# WallLightRemote_V1_0_HMI.net
KiCad netlist of a schematic drawn in Altium Designer
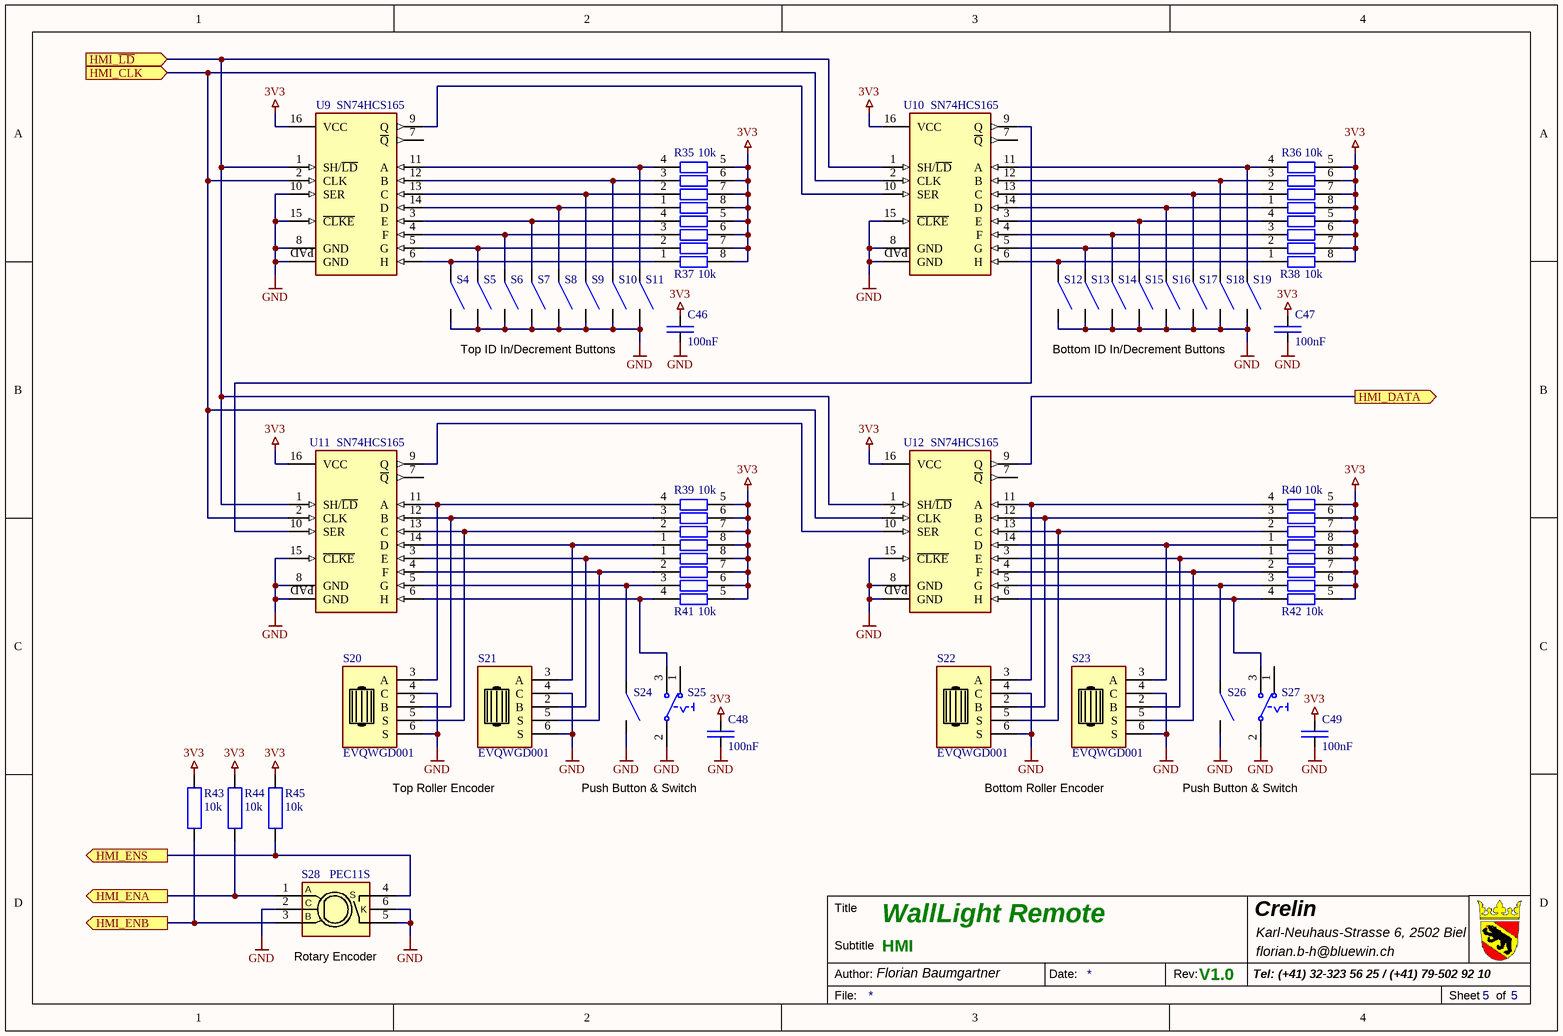
[diagram p0: WallLightRemote_V1.0_HMI.SchDoc]

(export (version "E")
  (design (tool "Eeschema 10.0.6"))
  (components
    (comp (ref "C46")
      (value "100nF")
      (footprint "SMD Keramikkondensator 0603")
      (description "SMD Ceramic Capacitor E6")
      (libsource (lib "Ceramic Capacitors-E6") (part "E6 - 100nF"))
    )
    (comp (ref "C47")
      (value "100nF")
      (footprint "SMD Keramikkondensator 0603")
      (description "SMD Ceramic Capacitor E6")
      (libsource (lib "Ceramic Capacitors-E6") (part "E6 - 100nF"))
    )
    (comp (ref "C48")
      (value "100nF")
      (footprint "SMD Keramikkondensator 0603")
      (description "SMD Ceramic Capacitor E6")
      (libsource (lib "Ceramic Capacitors-E6") (part "E6 - 100nF"))
    )
    (comp (ref "C49")
      (value "100nF")
      (footprint "SMD Keramikkondensator 0603")
      (description "SMD Ceramic Capacitor E6")
      (libsource (lib "Ceramic Capacitors-E6") (part "E6 - 100nF"))
    )
    (comp (ref "R35")
      (value "10k")
      (footprint "SMD Widerstand Array 4-Fach 0603")
      (description "Isolated Resistor Array")
      (libsource (lib "Fleet-Monitor") (part "R-Array Single Quad E24 - 10k"))
    )
    (comp (ref "R36")
      (value "10k")
      (footprint "SMD Widerstand Array 4-Fach 0603")
      (description "Isolated Resistor Array")
      (libsource (lib "Fleet-Monitor") (part "R-Array Single Quad E24 - 10k"))
    )
    (comp (ref "R37")
      (value "10k")
      (footprint "SMD Widerstand Array 4-Fach 0603")
      (description "Isolated Resistor Array")
      (libsource (lib "Fleet-Monitor") (part "R-Array Single Quad E24 - 10k"))
    )
    (comp (ref "R38")
      (value "10k")
      (footprint "SMD Widerstand Array 4-Fach 0603")
      (description "Isolated Resistor Array")
      (libsource (lib "Fleet-Monitor") (part "R-Array Single Quad E24 - 10k"))
    )
    (comp (ref "R39")
      (value "10k")
      (footprint "SMD Widerstand Array 4-Fach 0603")
      (description "Isolated Resistor Array")
      (libsource (lib "Fleet-Monitor") (part "R-Array Single Quad E24 - 10k"))
    )
    (comp (ref "R40")
      (value "10k")
      (footprint "SMD Widerstand Array 4-Fach 0603")
      (description "Isolated Resistor Array")
      (libsource (lib "Fleet-Monitor") (part "R-Array Single Quad E24 - 10k"))
    )
    (comp (ref "R41")
      (value "10k")
      (footprint "SMD Widerstand Array 4-Fach 0603")
      (description "Isolated Resistor Array")
      (libsource (lib "") (part "R-Array Single Quad E24 - 10k_1"))
    )
    (comp (ref "R42")
      (value "10k")
      (footprint "SMD Widerstand Array 4-Fach 0603")
      (description "Isolated Resistor Array")
      (libsource (lib "") (part "R-Array Single Quad E24 - 10k_1"))
    )
    (comp (ref "R43")
      (value "10k")
      (footprint "SMD Widerstand 0603")
      (description "RES (E=Heizwiderstand B=Messwandler)")
      (libsource (lib "TFS Integrated Library") (part "R-RESISTOR"))
    )
    (comp (ref "R44")
      (value "10k")
      (footprint "SMD Widerstand 0603")
      (description "RES (E=Heizwiderstand B=Messwandler)")
      (libsource (lib "TFS Integrated Library") (part "R-RESISTOR"))
    )
    (comp (ref "R45")
      (value "10k")
      (footprint "SMD Widerstand 0603")
      (description "RES (E=Heizwiderstand B=Messwandler)")
      (libsource (lib "TFS Integrated Library") (part "R-RESISTOR"))
    )
    (comp (ref "S4")
      (value "SMD-Button")
      (footprint "SMD Button 6.5x6.0x2.5")
      (description "Button SPST")
      (libsource (lib "Switches") (part "Button 3mmx2.5mm"))
    )
    (comp (ref "S5")
      (value "SMD-Button")
      (footprint "SMD Button 6.5x6.0x2.5")
      (description "Button SPST")
      (libsource (lib "Switches") (part "Button 3mmx2.5mm"))
    )
    (comp (ref "S6")
      (value "SMD-Button")
      (footprint "SMD Button 6.5x6.0x2.5")
      (description "Button SPST")
      (libsource (lib "Switches") (part "Button 3mmx2.5mm"))
    )
    (comp (ref "S7")
      (value "SMD-Button")
      (footprint "SMD Button 6.5x6.0x2.5")
      (description "Button SPST")
      (libsource (lib "Switches") (part "Button 3mmx2.5mm"))
    )
    (comp (ref "S8")
      (value "SMD-Button")
      (footprint "SMD Button 6.5x6.0x2.5")
      (description "Button SPST")
      (libsource (lib "Switches") (part "Button 3mmx2.5mm"))
    )
    (comp (ref "S9")
      (value "SMD-Button")
      (footprint "SMD Button 6.5x6.0x2.5")
      (description "Button SPST")
      (libsource (lib "Switches") (part "Button 3mmx2.5mm"))
    )
    (comp (ref "S10")
      (value "SMD-Button")
      (footprint "SMD Button 6.5x6.0x2.5")
      (description "Button SPST")
      (libsource (lib "Switches") (part "Button 3mmx2.5mm"))
    )
    (comp (ref "S11")
      (value "SMD-Button")
      (footprint "SMD Button 6.5x6.0x2.5")
      (description "Button SPST")
      (libsource (lib "Switches") (part "Button 3mmx2.5mm"))
    )
    (comp (ref "S12")
      (value "SMD-Button")
      (footprint "SMD Button 6.5x6.0x2.5")
      (description "Button SPST")
      (libsource (lib "Switches") (part "Button 3mmx2.5mm"))
    )
    (comp (ref "S13")
      (value "SMD-Button")
      (footprint "SMD Button 6.5x6.0x2.5")
      (description "Button SPST")
      (libsource (lib "Switches") (part "Button 3mmx2.5mm"))
    )
    (comp (ref "S14")
      (value "SMD-Button")
      (footprint "SMD Button 6.5x6.0x2.5")
      (description "Button SPST")
      (libsource (lib "Switches") (part "Button 3mmx2.5mm"))
    )
    (comp (ref "S15")
      (value "SMD-Button")
      (footprint "SMD Button 6.5x6.0x2.5")
      (description "Button SPST")
      (libsource (lib "Switches") (part "Button 3mmx2.5mm"))
    )
    (comp (ref "S16")
      (value "SMD-Button")
      (footprint "SMD Button 6.5x6.0x2.5")
      (description "Button SPST")
      (libsource (lib "Switches") (part "Button 3mmx2.5mm"))
    )
    (comp (ref "S17")
      (value "SMD-Button")
      (footprint "SMD Button 6.5x6.0x2.5")
      (description "Button SPST")
      (libsource (lib "Switches") (part "Button 3mmx2.5mm"))
    )
    (comp (ref "S18")
      (value "SMD-Button")
      (footprint "SMD Button 6.5x6.0x2.5")
      (description "Button SPST")
      (libsource (lib "Switches") (part "Button 3mmx2.5mm"))
    )
    (comp (ref "S19")
      (value "SMD-Button")
      (footprint "SMD Button 6.5x6.0x2.5")
      (description "Button SPST")
      (libsource (lib "Switches") (part "Button 3mmx2.5mm"))
    )
    (comp (ref "S20")
      (value "EVQWGD001")
      (footprint "THT Roller Encoder (EVQWGD001)")
      (description "Axial Roller Encoder")
      (libsource (lib "WallLightRemote") (part "S-EVQWGD001"))
    )
    (comp (ref "S21")
      (value "EVQWGD001")
      (footprint "THT Roller Encoder (EVQWGD001)")
      (description "Axial Roller Encoder")
      (libsource (lib "WallLightRemote") (part "S-EVQWGD001"))
    )
    (comp (ref "S22")
      (value "EVQWGD001")
      (footprint "THT Roller Encoder (EVQWGD001)")
      (description "Axial Roller Encoder")
      (libsource (lib "WallLightRemote") (part "S-EVQWGD001"))
    )
    (comp (ref "S23")
      (value "EVQWGD001")
      (footprint "THT Roller Encoder (EVQWGD001)")
      (description "Axial Roller Encoder")
      (libsource (lib "WallLightRemote") (part "S-EVQWGD001"))
    )
    (comp (ref "S24")
      (value "SMD-Button")
      (footprint "SMD Button 12.0x12.0x7.5")
      (description "Button SPST")
      (libsource (lib "Switches") (part "Button 3mmx2.5mm"))
    )
    (comp (ref "S25")
      (value "SS-12M11G5")
      (footprint "THT Slide Switch (MS12ANG03)")
      (description "Vertical Slide Switch SPDT")
      (libsource (lib "Custom ST-Link") (part "S-PCM12SMTR"))
    )
    (comp (ref "S26")
      (value "SMD-Button")
      (footprint "SMD Button 12.0x12.0x7.5")
      (description "Button SPST")
      (libsource (lib "Switches") (part "Button 3mmx2.5mm"))
    )
    (comp (ref "S27")
      (value "SS-12M11G5")
      (footprint "THT Slide Switch (MS12ANG03)")
      (description "Vertical Slide Switch SPDT")
      (libsource (lib "Custom ST-Link") (part "S-PCM12SMTR"))
    )
    (comp (ref "S28")
      (value "PEC11S")
      (footprint "SMD Rotary Encoder with Switch")
      (description "Rotary Encoder")
      (libsource (lib "WallLightRemote") (part "S-Rotary Encoder"))
    )
    (comp (ref "U9")
      (value "SN74HCS165")
      (footprint "SMD IC WQFN-16 (3.5x2.5)")
      (description "8-Bit Paralell-In Shift Register (Schmitt Trigger)")
      (libsource (lib "WallLightRemote") (part "U-SN74HCS165"))
    )
    (comp (ref "U10")
      (value "SN74HCS165")
      (footprint "SMD IC WQFN-16 (3.5x2.5)")
      (description "8-Bit Paralell-In Shift Register (Schmitt Trigger)")
      (libsource (lib "WallLightRemote") (part "U-SN74HCS165"))
    )
    (comp (ref "U11")
      (value "SN74HCS165")
      (footprint "SMD IC WQFN-16 (3.5x2.5)")
      (description "8-Bit Paralell-In Shift Register (Schmitt Trigger)")
      (libsource (lib "WallLightRemote") (part "U-SN74HCS165"))
    )
    (comp (ref "U12")
      (value "SN74HCS165")
      (footprint "SMD IC WQFN-16 (3.5x2.5)")
      (description "8-Bit Paralell-In Shift Register (Schmitt Trigger)")
      (libsource (lib "WallLightRemote") (part "U-SN74HCS165"))
    )
  )
  (nets
    (net (code "1") (name "/HMI_CLK") (class "Default")
      (node (ref "U10") (pin "2") (pinfunction "CLK_2") (pintype "input"))
      (node (ref "U11") (pin "2") (pinfunction "CLK_2") (pintype "input"))
      (node (ref "U12") (pin "2") (pinfunction "CLK_2") (pintype "input"))
      (node (ref "U9") (pin "2") (pinfunction "CLK_2") (pintype "input"))
    )
    (net (code "2") (name "/HMI_DATA") (class "Default")
      (node (ref "U12") (pin "9") (pinfunction "Q_9") (pintype "output"))
    )
    (net (code "3") (name "/HMI_ENA") (class "Default")
      (node (ref "R44") (pin "1") (pinfunction "1_1") (pintype "passive"))
      (node (ref "S28") (pin "1") (pinfunction "A_1") (pintype "passive"))
    )
    (net (code "4") (name "/HMI_ENB") (class "Default")
      (node (ref "R43") (pin "1") (pinfunction "1_1") (pintype "passive"))
      (node (ref "S28") (pin "3") (pinfunction "B_3") (pintype "passive"))
    )
    (net (code "5") (name "/HMI_ENS") (class "Default")
      (node (ref "R45") (pin "1") (pinfunction "1_1") (pintype "passive"))
      (node (ref "S28") (pin "4") (pinfunction "S_4") (pintype "passive"))
    )
    (net (code "6") (name "/HMI_~{LD}") (class "Default")
      (node (ref "U10") (pin "1") (pinfunction "SH/~{LD}_1") (pintype "input"))
      (node (ref "U11") (pin "1") (pinfunction "SH/~{LD}_1") (pintype "input"))
      (node (ref "U12") (pin "1") (pinfunction "SH/~{LD}_1") (pintype "input"))
      (node (ref "U9") (pin "1") (pinfunction "SH/~{LD}_1") (pintype "input"))
    )
    (net (code "7") (name "3V3") (class "Default")
      (node (ref "C46") (pin "2") (pinfunction "2_2") (pintype "passive"))
      (node (ref "C47") (pin "2") (pinfunction "2_2") (pintype "passive"))
      (node (ref "C48") (pin "2") (pinfunction "2_2") (pintype "passive"))
      (node (ref "C49") (pin "2") (pinfunction "2_2") (pintype "passive"))
      (node (ref "R35") (pin "5") (pinfunction "5_5") (pintype "passive"))
      (node (ref "R35") (pin "6") (pinfunction "6_6") (pintype "passive"))
      (node (ref "R35") (pin "7") (pinfunction "7_7") (pintype "passive"))
      (node (ref "R35") (pin "8") (pinfunction "8_8") (pintype "passive"))
      (node (ref "R36") (pin "5") (pinfunction "5_5") (pintype "passive"))
      (node (ref "R36") (pin "6") (pinfunction "6_6") (pintype "passive"))
      (node (ref "R36") (pin "7") (pinfunction "7_7") (pintype "passive"))
      (node (ref "R36") (pin "8") (pinfunction "8_8") (pintype "passive"))
      (node (ref "R37") (pin "5") (pinfunction "5_5") (pintype "passive"))
      (node (ref "R37") (pin "6") (pinfunction "6_6") (pintype "passive"))
      (node (ref "R37") (pin "7") (pinfunction "7_7") (pintype "passive"))
      (node (ref "R37") (pin "8") (pinfunction "8_8") (pintype "passive"))
      (node (ref "R38") (pin "5") (pinfunction "5_5") (pintype "passive"))
      (node (ref "R38") (pin "6") (pinfunction "6_6") (pintype "passive"))
      (node (ref "R38") (pin "7") (pinfunction "7_7") (pintype "passive"))
      (node (ref "R38") (pin "8") (pinfunction "8_8") (pintype "passive"))
      (node (ref "R39") (pin "5") (pinfunction "5_5") (pintype "passive"))
      (node (ref "R39") (pin "6") (pinfunction "6_6") (pintype "passive"))
      (node (ref "R39") (pin "7") (pinfunction "7_7") (pintype "passive"))
      (node (ref "R39") (pin "8") (pinfunction "8_8") (pintype "passive"))
      (node (ref "R40") (pin "5") (pinfunction "5_5") (pintype "passive"))
      (node (ref "R40") (pin "6") (pinfunction "6_6") (pintype "passive"))
      (node (ref "R40") (pin "7") (pinfunction "7_7") (pintype "passive"))
      (node (ref "R40") (pin "8") (pinfunction "8_8") (pintype "passive"))
      (node (ref "R41") (pin "5") (pinfunction "5_5") (pintype "passive"))
      (node (ref "R41") (pin "6") (pinfunction "6_6") (pintype "passive"))
      (node (ref "R41") (pin "7") (pinfunction "7_7") (pintype "passive"))
      (node (ref "R41") (pin "8") (pinfunction "8_8") (pintype "passive"))
      (node (ref "R42") (pin "5") (pinfunction "5_5") (pintype "passive"))
      (node (ref "R42") (pin "6") (pinfunction "6_6") (pintype "passive"))
      (node (ref "R42") (pin "7") (pinfunction "7_7") (pintype "passive"))
      (node (ref "R42") (pin "8") (pinfunction "8_8") (pintype "passive"))
      (node (ref "R43") (pin "2") (pinfunction "2_2") (pintype "passive"))
      (node (ref "R44") (pin "2") (pinfunction "2_2") (pintype "passive"))
      (node (ref "R45") (pin "2") (pinfunction "2_2") (pintype "passive"))
      (node (ref "U10") (pin "16") (pinfunction "VCC_16") (pintype "power_in"))
      (node (ref "U11") (pin "16") (pinfunction "VCC_16") (pintype "power_in"))
      (node (ref "U12") (pin "16") (pinfunction "VCC_16") (pintype "power_in"))
      (node (ref "U9") (pin "16") (pinfunction "VCC_16") (pintype "power_in"))
    )
    (net (code "8") (name "GND") (class "Default")
      (node (ref "C46") (pin "1") (pinfunction "1_1") (pintype "passive"))
      (node (ref "C47") (pin "1") (pinfunction "1_1") (pintype "passive"))
      (node (ref "C48") (pin "1") (pinfunction "1_1") (pintype "passive"))
      (node (ref "C49") (pin "1") (pinfunction "1_1") (pintype "passive"))
      (node (ref "S10") (pin "2") (pinfunction "2_2") (pintype "passive"))
      (node (ref "S11") (pin "2") (pinfunction "2_2") (pintype "passive"))
      (node (ref "S12") (pin "2") (pinfunction "2_2") (pintype "passive"))
      (node (ref "S13") (pin "2") (pinfunction "2_2") (pintype "passive"))
      (node (ref "S14") (pin "2") (pinfunction "2_2") (pintype "passive"))
      (node (ref "S15") (pin "2") (pinfunction "2_2") (pintype "passive"))
      (node (ref "S16") (pin "2") (pinfunction "2_2") (pintype "passive"))
      (node (ref "S17") (pin "2") (pinfunction "2_2") (pintype "passive"))
      (node (ref "S18") (pin "2") (pinfunction "2_2") (pintype "passive"))
      (node (ref "S19") (pin "2") (pinfunction "2_2") (pintype "passive"))
      (node (ref "S20") (pin "4") (pinfunction "C_4") (pintype "passive"))
      (node (ref "S20") (pin "6") (pinfunction "S_6") (pintype "passive"))
      (node (ref "S21") (pin "4") (pinfunction "C_4") (pintype "passive"))
      (node (ref "S21") (pin "6") (pinfunction "S_6") (pintype "passive"))
      (node (ref "S22") (pin "4") (pinfunction "C_4") (pintype "passive"))
      (node (ref "S22") (pin "6") (pinfunction "S_6") (pintype "passive"))
      (node (ref "S23") (pin "4") (pinfunction "C_4") (pintype "passive"))
      (node (ref "S23") (pin "6") (pinfunction "S_6") (pintype "passive"))
      (node (ref "S24") (pin "2") (pinfunction "2_2") (pintype "passive"))
      (node (ref "S25") (pin "2") (pinfunction "COMMON1_2") (pintype "passive"))
      (node (ref "S26") (pin "2") (pinfunction "2_2") (pintype "passive"))
      (node (ref "S27") (pin "2") (pinfunction "COMMON1_2") (pintype "passive"))
      (node (ref "S28") (pin "2") (pinfunction "C_2") (pintype "passive"))
      (node (ref "S28") (pin "5") (pinfunction "S_5") (pintype "passive"))
      (node (ref "S28") (pin "6") (pinfunction "K_6") (pintype "passive"))
      (node (ref "S4") (pin "2") (pinfunction "2_2") (pintype "passive"))
      (node (ref "S5") (pin "2") (pinfunction "2_2") (pintype "passive"))
      (node (ref "S6") (pin "2") (pinfunction "2_2") (pintype "passive"))
      (node (ref "S7") (pin "2") (pinfunction "2_2") (pintype "passive"))
      (node (ref "S8") (pin "2") (pinfunction "2_2") (pintype "passive"))
      (node (ref "S9") (pin "2") (pinfunction "2_2") (pintype "passive"))
      (node (ref "U10") (pin "15") (pinfunction "~{CLKE}_15") (pintype "input"))
      (node (ref "U10") (pin "8") (pinfunction "GND_8") (pintype "power_in"))
      (node (ref "U10") (pin "PAD") (pinfunction "GND_PAD") (pintype "power_in"))
      (node (ref "U11") (pin "15") (pinfunction "~{CLKE}_15") (pintype "input"))
      (node (ref "U11") (pin "8") (pinfunction "GND_8") (pintype "power_in"))
      (node (ref "U11") (pin "PAD") (pinfunction "GND_PAD") (pintype "power_in"))
      (node (ref "U12") (pin "15") (pinfunction "~{CLKE}_15") (pintype "input"))
      (node (ref "U12") (pin "8") (pinfunction "GND_8") (pintype "power_in"))
      (node (ref "U12") (pin "PAD") (pinfunction "GND_PAD") (pintype "power_in"))
      (node (ref "U9") (pin "10") (pinfunction "SER_10") (pintype "input"))
      (node (ref "U9") (pin "15") (pinfunction "~{CLKE}_15") (pintype "input"))
      (node (ref "U9") (pin "8") (pinfunction "GND_8") (pintype "power_in"))
      (node (ref "U9") (pin "PAD") (pinfunction "GND_PAD") (pintype "power_in"))
    )
    (net (code "9") (name "Net-(S20-A)") (class "Default")
      (node (ref "R39") (pin "4") (pinfunction "4_4") (pintype "passive"))
      (node (ref "S20") (pin "3") (pinfunction "A_3") (pintype "passive"))
      (node (ref "U11") (pin "11") (pinfunction "A_11") (pintype "input"))
    )
    (net (code "10") (name "Net-(S20-B)") (class "Default")
      (node (ref "R39") (pin "3") (pinfunction "3_3") (pintype "passive"))
      (node (ref "S20") (pin "2") (pinfunction "B_2") (pintype "passive"))
      (node (ref "U11") (pin "12") (pinfunction "B_12") (pintype "input"))
    )
    (net (code "11") (name "Net-(S21-A)") (class "Default")
      (node (ref "R39") (pin "1") (pinfunction "1_1") (pintype "passive"))
      (node (ref "S21") (pin "3") (pinfunction "A_3") (pintype "passive"))
      (node (ref "U11") (pin "14") (pinfunction "D_14") (pintype "input"))
    )
    (net (code "12") (name "Net-(S21-B)") (class "Default")
      (node (ref "R41") (pin "1") (pinfunction "1_1") (pintype "passive"))
      (node (ref "S21") (pin "2") (pinfunction "B_2") (pintype "passive"))
      (node (ref "U11") (pin "3") (pinfunction "E_3") (pintype "input"))
    )
    (net (code "13") (name "Net-(S22-A)") (class "Default")
      (node (ref "R40") (pin "4") (pinfunction "4_4") (pintype "passive"))
      (node (ref "S22") (pin "3") (pinfunction "A_3") (pintype "passive"))
      (node (ref "U12") (pin "11") (pinfunction "A_11") (pintype "input"))
    )
    (net (code "14") (name "Net-(S22-B)") (class "Default")
      (node (ref "R40") (pin "3") (pinfunction "3_3") (pintype "passive"))
      (node (ref "S22") (pin "2") (pinfunction "B_2") (pintype "passive"))
      (node (ref "U12") (pin "12") (pinfunction "B_12") (pintype "input"))
    )
    (net (code "15") (name "Net-(S23-A)") (class "Default")
      (node (ref "R40") (pin "1") (pinfunction "1_1") (pintype "passive"))
      (node (ref "S23") (pin "3") (pinfunction "A_3") (pintype "passive"))
      (node (ref "U12") (pin "14") (pinfunction "D_14") (pintype "input"))
    )
    (net (code "16") (name "Net-(S23-B)") (class "Default")
      (node (ref "R42") (pin "1") (pinfunction "1_1") (pintype "passive"))
      (node (ref "S23") (pin "2") (pinfunction "B_2") (pintype "passive"))
      (node (ref "U12") (pin "3") (pinfunction "E_3") (pintype "input"))
    )
    (net (code "17") (name "Net-(S25-NO1)") (class "Default")
      (node (ref "R41") (pin "4") (pinfunction "4_4") (pintype "passive"))
      (node (ref "S25") (pin "3") (pinfunction "NO1_3") (pintype "passive"))
      (node (ref "U11") (pin "6") (pinfunction "H_6") (pintype "input"))
    )
    (net (code "18") (name "Net-(S27-NO1)") (class "Default")
      (node (ref "R42") (pin "4") (pinfunction "4_4") (pintype "passive"))
      (node (ref "S27") (pin "3") (pinfunction "NO1_3") (pintype "passive"))
      (node (ref "U12") (pin "6") (pinfunction "H_6") (pintype "input"))
    )
    (net (code "19") (name "Net-(U9-A)") (class "Default")
      (node (ref "R35") (pin "4") (pinfunction "4_4") (pintype "passive"))
      (node (ref "S11") (pin "1") (pinfunction "1_1") (pintype "passive"))
      (node (ref "U9") (pin "11") (pinfunction "A_11") (pintype "input"))
    )
    (net (code "20") (name "Net-(U9-B)") (class "Default")
      (node (ref "R35") (pin "3") (pinfunction "3_3") (pintype "passive"))
      (node (ref "S10") (pin "1") (pinfunction "1_1") (pintype "passive"))
      (node (ref "U9") (pin "12") (pinfunction "B_12") (pintype "input"))
    )
    (net (code "21") (name "Net-(U9-C)") (class "Default")
      (node (ref "R35") (pin "2") (pinfunction "2_2") (pintype "passive"))
      (node (ref "S9") (pin "1") (pinfunction "1_1") (pintype "passive"))
      (node (ref "U9") (pin "13") (pinfunction "C_13") (pintype "input"))
    )
    (net (code "22") (name "Net-(U9-D)") (class "Default")
      (node (ref "R35") (pin "1") (pinfunction "1_1") (pintype "passive"))
      (node (ref "S8") (pin "1") (pinfunction "1_1") (pintype "passive"))
      (node (ref "U9") (pin "14") (pinfunction "D_14") (pintype "input"))
    )
    (net (code "23") (name "Net-(U9-E)") (class "Default")
      (node (ref "R37") (pin "4") (pinfunction "4_4") (pintype "passive"))
      (node (ref "S7") (pin "1") (pinfunction "1_1") (pintype "passive"))
      (node (ref "U9") (pin "3") (pinfunction "E_3") (pintype "input"))
    )
    (net (code "24") (name "Net-(U9-F)") (class "Default")
      (node (ref "R37") (pin "3") (pinfunction "3_3") (pintype "passive"))
      (node (ref "S6") (pin "1") (pinfunction "1_1") (pintype "passive"))
      (node (ref "U9") (pin "4") (pinfunction "F_4") (pintype "input"))
    )
    (net (code "25") (name "Net-(U9-G)") (class "Default")
      (node (ref "R37") (pin "2") (pinfunction "2_2") (pintype "passive"))
      (node (ref "S5") (pin "1") (pinfunction "1_1") (pintype "passive"))
      (node (ref "U9") (pin "5") (pinfunction "G_5") (pintype "input"))
    )
    (net (code "26") (name "Net-(U9-H)") (class "Default")
      (node (ref "R37") (pin "1") (pinfunction "1_1") (pintype "passive"))
      (node (ref "S4") (pin "1") (pinfunction "1_1") (pintype "passive"))
      (node (ref "U9") (pin "6") (pinfunction "H_6") (pintype "input"))
    )
    (net (code "27") (name "Net-(U10-A)") (class "Default")
      (node (ref "R36") (pin "4") (pinfunction "4_4") (pintype "passive"))
      (node (ref "S19") (pin "1") (pinfunction "1_1") (pintype "passive"))
      (node (ref "U10") (pin "11") (pinfunction "A_11") (pintype "input"))
    )
    (net (code "28") (name "Net-(U10-B)") (class "Default")
      (node (ref "R36") (pin "3") (pinfunction "3_3") (pintype "passive"))
      (node (ref "S18") (pin "1") (pinfunction "1_1") (pintype "passive"))
      (node (ref "U10") (pin "12") (pinfunction "B_12") (pintype "input"))
    )
    (net (code "29") (name "Net-(U10-C)") (class "Default")
      (node (ref "R36") (pin "2") (pinfunction "2_2") (pintype "passive"))
      (node (ref "S17") (pin "1") (pinfunction "1_1") (pintype "passive"))
      (node (ref "U10") (pin "13") (pinfunction "C_13") (pintype "input"))
    )
    (net (code "30") (name "Net-(U10-D)") (class "Default")
      (node (ref "R36") (pin "1") (pinfunction "1_1") (pintype "passive"))
      (node (ref "S16") (pin "1") (pinfunction "1_1") (pintype "passive"))
      (node (ref "U10") (pin "14") (pinfunction "D_14") (pintype "input"))
    )
    (net (code "31") (name "Net-(U10-E)") (class "Default")
      (node (ref "R38") (pin "4") (pinfunction "4_4") (pintype "passive"))
      (node (ref "S15") (pin "1") (pinfunction "1_1") (pintype "passive"))
      (node (ref "U10") (pin "3") (pinfunction "E_3") (pintype "input"))
    )
    (net (code "32") (name "Net-(U10-F)") (class "Default")
      (node (ref "R38") (pin "3") (pinfunction "3_3") (pintype "passive"))
      (node (ref "S14") (pin "1") (pinfunction "1_1") (pintype "passive"))
      (node (ref "U10") (pin "4") (pinfunction "F_4") (pintype "input"))
    )
    (net (code "33") (name "Net-(U10-G)") (class "Default")
      (node (ref "R38") (pin "2") (pinfunction "2_2") (pintype "passive"))
      (node (ref "S13") (pin "1") (pinfunction "1_1") (pintype "passive"))
      (node (ref "U10") (pin "5") (pinfunction "G_5") (pintype "input"))
    )
    (net (code "34") (name "Net-(U10-H)") (class "Default")
      (node (ref "R38") (pin "1") (pinfunction "1_1") (pintype "passive"))
      (node (ref "S12") (pin "1") (pinfunction "1_1") (pintype "passive"))
      (node (ref "U10") (pin "6") (pinfunction "H_6") (pintype "input"))
    )
    (net (code "35") (name "Net-(U10-Q)") (class "Default")
      (node (ref "U10") (pin "9") (pinfunction "Q_9") (pintype "output"))
      (node (ref "U11") (pin "10") (pinfunction "SER_10") (pintype "input"))
    )
    (net (code "36") (name "Net-(U10-SER)") (class "Default")
      (node (ref "U10") (pin "10") (pinfunction "SER_10") (pintype "input"))
      (node (ref "U9") (pin "9") (pinfunction "Q_9") (pintype "output"))
    )
    (net (code "37") (name "Net-(U11-C)") (class "Default")
      (node (ref "R39") (pin "2") (pinfunction "2_2") (pintype "passive"))
      (node (ref "S20") (pin "5") (pinfunction "S_5") (pintype "passive"))
      (node (ref "U11") (pin "13") (pinfunction "C_13") (pintype "input"))
    )
    (net (code "38") (name "Net-(U11-F)") (class "Default")
      (node (ref "R41") (pin "2") (pinfunction "2_2") (pintype "passive"))
      (node (ref "S21") (pin "5") (pinfunction "S_5") (pintype "passive"))
      (node (ref "U11") (pin "4") (pinfunction "F_4") (pintype "input"))
    )
    (net (code "39") (name "Net-(U11-G)") (class "Default")
      (node (ref "R41") (pin "3") (pinfunction "3_3") (pintype "passive"))
      (node (ref "S24") (pin "1") (pinfunction "1_1") (pintype "passive"))
      (node (ref "U11") (pin "5") (pinfunction "G_5") (pintype "input"))
    )
    (net (code "40") (name "Net-(U11-Q)") (class "Default")
      (node (ref "U11") (pin "9") (pinfunction "Q_9") (pintype "output"))
      (node (ref "U12") (pin "10") (pinfunction "SER_10") (pintype "input"))
    )
    (net (code "41") (name "Net-(U12-C)") (class "Default")
      (node (ref "R40") (pin "2") (pinfunction "2_2") (pintype "passive"))
      (node (ref "S22") (pin "5") (pinfunction "S_5") (pintype "passive"))
      (node (ref "U12") (pin "13") (pinfunction "C_13") (pintype "input"))
    )
    (net (code "42") (name "Net-(U12-F)") (class "Default")
      (node (ref "R42") (pin "2") (pinfunction "2_2") (pintype "passive"))
      (node (ref "S23") (pin "5") (pinfunction "S_5") (pintype "passive"))
      (node (ref "U12") (pin "4") (pinfunction "F_4") (pintype "input"))
    )
    (net (code "43") (name "Net-(U12-G)") (class "Default")
      (node (ref "R42") (pin "3") (pinfunction "3_3") (pintype "passive"))
      (node (ref "S26") (pin "1") (pinfunction "1_1") (pintype "passive"))
      (node (ref "U12") (pin "5") (pinfunction "G_5") (pintype "input"))
    )
    (net (code "44") (name "unconnected-(S20-NC-Pad1)") (class "Default")
      (node (ref "S20") (pin "1") (pinfunction "NC_1") (pintype "passive"))
    )
    (net (code "45") (name "unconnected-(S21-NC-Pad1)") (class "Default")
      (node (ref "S21") (pin "1") (pinfunction "NC_1") (pintype "passive"))
    )
    (net (code "46") (name "unconnected-(S22-NC-Pad1)") (class "Default")
      (node (ref "S22") (pin "1") (pinfunction "NC_1") (pintype "passive"))
    )
    (net (code "47") (name "unconnected-(S23-NC-Pad1)") (class "Default")
      (node (ref "S23") (pin "1") (pinfunction "NC_1") (pintype "passive"))
    )
    (net (code "48") (name "unconnected-(S25-NC1-Pad1)") (class "Default")
      (node (ref "S25") (pin "1") (pinfunction "NC1_1") (pintype "passive"))
    )
    (net (code "49") (name "unconnected-(S27-NC1-Pad1)") (class "Default")
      (node (ref "S27") (pin "1") (pinfunction "NC1_1") (pintype "passive"))
    )
    (net (code "50") (name "unconnected-(U9-~{Q}-Pad7)") (class "Default")
      (node (ref "U9") (pin "7") (pinfunction "~{Q}_7") (pintype "output"))
    )
    (net (code "51") (name "unconnected-(U10-~{Q}-Pad7)") (class "Default")
      (node (ref "U10") (pin "7") (pinfunction "~{Q}_7") (pintype "output"))
    )
    (net (code "52") (name "unconnected-(U11-~{Q}-Pad7)") (class "Default")
      (node (ref "U11") (pin "7") (pinfunction "~{Q}_7") (pintype "output"))
    )
    (net (code "53") (name "unconnected-(U12-~{Q}-Pad7)") (class "Default")
      (node (ref "U12") (pin "7") (pinfunction "~{Q}_7") (pintype "output"))
    )
  )
)
